# RF_433MHz.net
KiCad netlist of a schematic drawn in Altium Designer
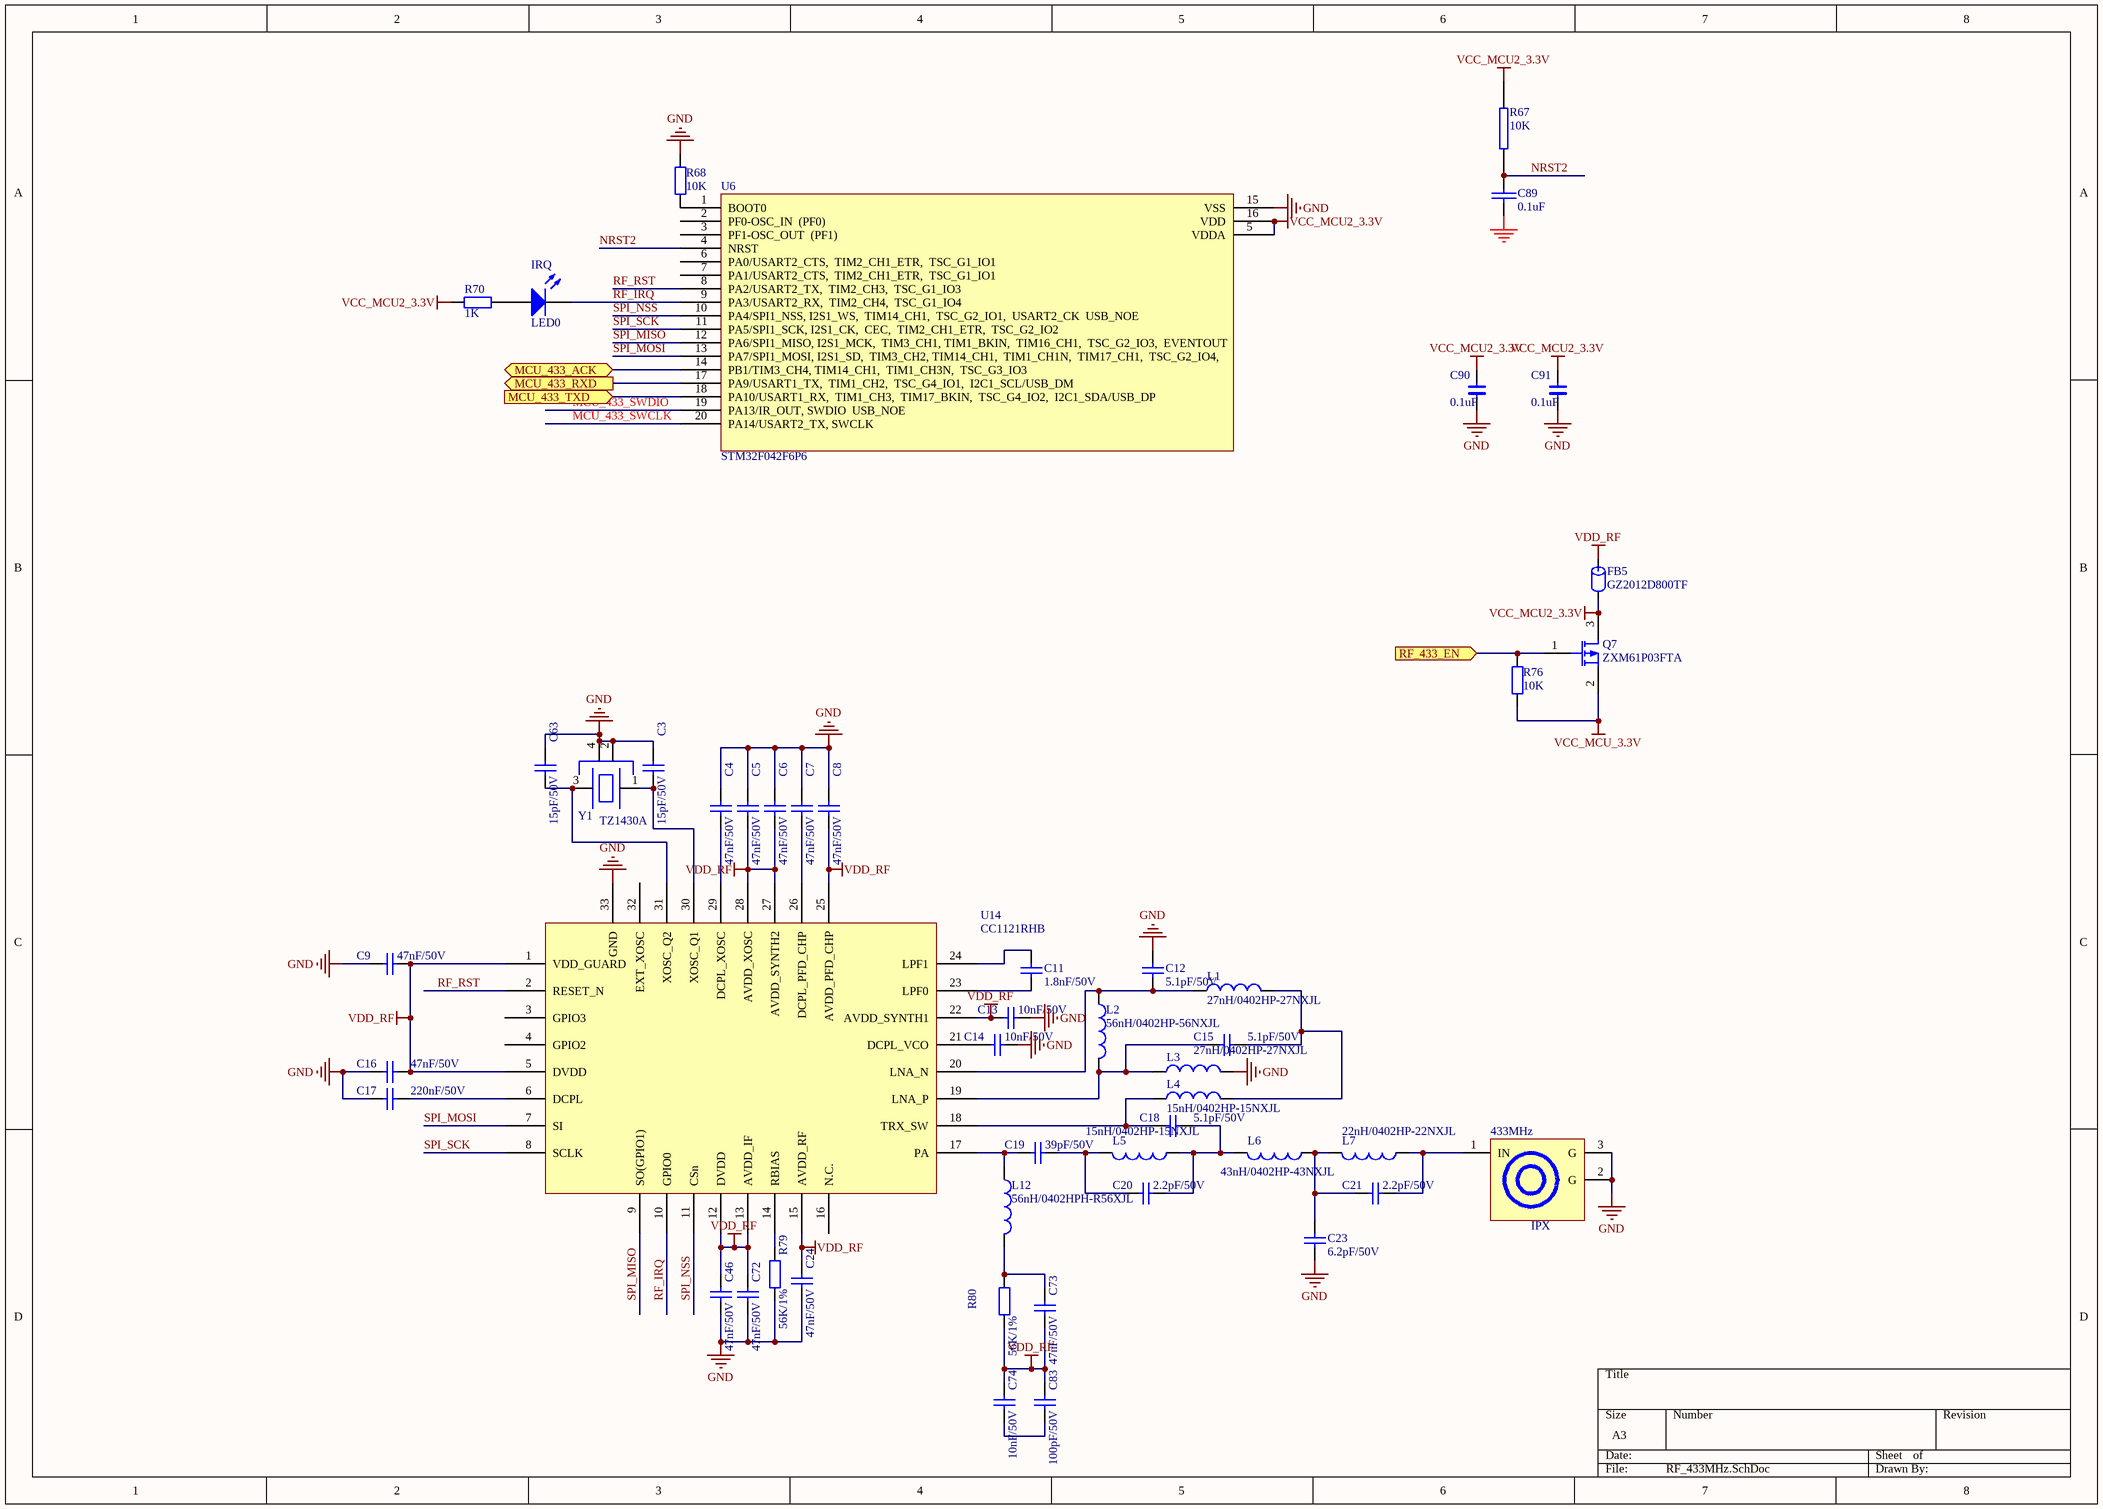
[diagram p0: RF_433MHz.SchDoc]

(export (version "E")
  (design (tool "Eeschema 10.0.6"))
  (components
    (comp (ref "433MHz")
      (value "IPX")
      (footprint "Pcblib_20110825:ECT8180001581")
      (description "MCU")
      (libsource (lib "MCU") (part "IPX"))
    )
    (comp (ref "C3")
      (value "15pF/50V")
      (footprint "0402C")
      (description "Capacitor SMD")
      (fields (field (name "PUBLISHER") "Altium Limited"))
      (libsource (lib "SX1276_e266v02a") (part "Cap"))
    )
    (comp (ref "C4")
      (value "47nF/50V")
      (footprint "0402C")
      (description "Capacitor SMD")
      (fields (field (name "PUBLISHER") "Altium Limited"))
      (libsource (lib "SX1276_e266v02a") (part "Cap"))
    )
    (comp (ref "C5")
      (value "47nF/50V")
      (footprint "0402C")
      (description "Capacitor SMD")
      (fields (field (name "PUBLISHER") "Altium Limited"))
      (libsource (lib "SX1276_e266v02a") (part "Cap"))
    )
    (comp (ref "C6")
      (value "47nF/50V")
      (footprint "0402C")
      (description "Capacitor SMD")
      (fields (field (name "PUBLISHER") "Altium Limited"))
      (libsource (lib "SX1276_e266v02a") (part "Cap"))
    )
    (comp (ref "C7")
      (value "47nF/50V")
      (footprint "0402C")
      (description "Capacitor SMD")
      (fields (field (name "PUBLISHER") "Altium Limited"))
      (libsource (lib "SX1276_e266v02a") (part "Cap"))
    )
    (comp (ref "C8")
      (value "47nF/50V")
      (footprint "0402C")
      (description "Capacitor SMD")
      (fields (field (name "PUBLISHER") "Altium Limited"))
      (libsource (lib "SX1276_e266v02a") (part "Cap"))
    )
    (comp (ref "C9")
      (value "47nF/50V")
      (footprint "0402C")
      (description "Capacitor SMD")
      (fields (field (name "PUBLISHER") "Altium Limited"))
      (libsource (lib "SX1276_e266v02a") (part "Cap"))
    )
    (comp (ref "C11")
      (value "1.8nF/50V")
      (footprint "0402C")
      (description "Capacitor SMD")
      (fields (field (name "PUBLISHER") "Altium Limited"))
      (libsource (lib "SX1276_e266v02a") (part "Cap"))
    )
    (comp (ref "C12")
      (value "5.1pF/50V")
      (footprint "0402C")
      (description "Capacitor SMD")
      (fields (field (name "PUBLISHER") "Altium Limited"))
      (libsource (lib "SX1276_e266v02a") (part "Cap"))
    )
    (comp (ref "C13")
      (value "10nF/50V")
      (footprint "0402C")
      (description "Capacitor SMD")
      (fields (field (name "PUBLISHER") "Altium Limited"))
      (libsource (lib "SX1276_e266v02a") (part "Cap"))
    )
    (comp (ref "C14")
      (value "10nF/50V")
      (footprint "0402C")
      (description "Capacitor SMD")
      (fields (field (name "PUBLISHER") "Altium Limited"))
      (libsource (lib "SX1276_e266v02a") (part "Cap"))
    )
    (comp (ref "C15")
      (value "5.1pF/50V")
      (footprint "0402C")
      (description "Capacitor SMD")
      (fields (field (name "PUBLISHER") "Altium Limited"))
      (libsource (lib "SX1276_e266v02a") (part "Cap"))
    )
    (comp (ref "C16")
      (value "47nF/50V")
      (footprint "0402C")
      (description "Capacitor SMD")
      (fields (field (name "PUBLISHER") "Altium Limited"))
      (libsource (lib "SX1276_e266v02a") (part "Cap"))
    )
    (comp (ref "C17")
      (value "220nF/50V")
      (footprint "0402C")
      (description "Capacitor SMD")
      (fields (field (name "PUBLISHER") "Altium Limited"))
      (libsource (lib "SX1276_e266v02a") (part "Cap"))
    )
    (comp (ref "C18")
      (value "5.1pF/50V")
      (footprint "0402C")
      (description "Capacitor SMD")
      (fields (field (name "PUBLISHER") "Altium Limited"))
      (libsource (lib "SX1276_e266v02a") (part "Cap"))
    )
    (comp (ref "C19")
      (value "39pF/50V")
      (footprint "0402C")
      (description "Capacitor SMD")
      (fields (field (name "PUBLISHER") "Altium Limited"))
      (libsource (lib "SX1276_e266v02a") (part "Cap"))
    )
    (comp (ref "C20")
      (value "2.2pF/50V")
      (footprint "0402C")
      (description "Capacitor SMD")
      (fields (field (name "PUBLISHER") "Altium Limited"))
      (libsource (lib "SX1276_e266v02a") (part "Cap"))
    )
    (comp (ref "C21")
      (value "2.2pF/50V")
      (footprint "0402C")
      (description "Capacitor SMD")
      (fields (field (name "PUBLISHER") "Altium Limited"))
      (libsource (lib "SX1276_e266v02a") (part "Cap"))
    )
    (comp (ref "C23")
      (value "6.2pF/50V")
      (footprint "0402C")
      (description "Capacitor SMD")
      (fields (field (name "PUBLISHER") "Altium Limited"))
      (libsource (lib "SX1276_e266v02a") (part "Cap"))
    )
    (comp (ref "C24")
      (value "47nF/50V")
      (footprint "0402C")
      (description "Capacitor SMD")
      (fields (field (name "PUBLISHER") "Altium Limited"))
      (libsource (lib "SX1276_e266v02a") (part "Cap"))
    )
    (comp (ref "C46")
      (value "47nF/50V")
      (footprint "0402C")
      (description "Capacitor SMD")
      (fields (field (name "PUBLISHER") "Altium Limited"))
      (libsource (lib "SX1276_e266v02a") (part "Cap"))
    )
    (comp (ref "C63")
      (value "15pF/50V")
      (footprint "0402C")
      (description "Capacitor SMD")
      (fields (field (name "PUBLISHER") "Altium Limited"))
      (libsource (lib "SX1276_e266v02a") (part "Cap"))
    )
    (comp (ref "C72")
      (value "47nF/50V")
      (footprint "0402C")
      (description "Capacitor SMD")
      (fields (field (name "PUBLISHER") "Altium Limited"))
      (libsource (lib "SX1276_e266v02a") (part "Cap"))
    )
    (comp (ref "C73")
      (value "47nF/50V")
      (footprint "0402C")
      (description "Capacitor SMD")
      (fields (field (name "PUBLISHER") "Altium Limited"))
      (libsource (lib "SX1276_e266v02a") (part "Cap"))
    )
    (comp (ref "C74")
      (value "10nF/50V")
      (footprint "0402C")
      (description "Capacitor SMD")
      (fields (field (name "PUBLISHER") "Altium Limited"))
      (libsource (lib "SX1276_e266v02a") (part "Cap"))
    )
    (comp (ref "C83")
      (value "100pF/50V")
      (footprint "0402C")
      (description "Capacitor SMD")
      (fields (field (name "PUBLISHER") "Altium Limited"))
      (libsource (lib "SX1276_e266v02a") (part "Cap"))
    )
    (comp (ref "C89")
      (value "0.1uF")
      (footprint "0603C")
      (description "Capacitor")
      (libsource (lib "*") (part "CAP"))
    )
    (comp (ref "C90")
      (value "0.1uF")
      (footprint "0603C")
      (description "C")
      (libsource (lib "Schlib_20110825") (part "C"))
    )
    (comp (ref "C91")
      (value "0.1uF")
      (footprint "0603C")
      (description "C")
      (libsource (lib "Schlib_20110825") (part "C"))
    )
    (comp (ref "FB5")
      (value "GZ2012D800TF")
      (footprint "0805CZ")
      (libsource (lib "Schlib_20110825") (part "FB"))
    )
    (comp (ref "IRQ")
      (value "LED0")
      (footprint "0603LED")
      (description "Typical INFRARED GaAs LED")
      (fields (field (name "PUBLISHER") "Altium Limited"))
      (libsource (lib "Miscellaneous Devices") (part "LED0"))
    )
    (comp (ref "L1")
      (value "27nH/0402HP-27NXJL")
      (footprint "0402R")
      (description "Inductor SMD")
      (fields (field (name "PUBLISHER") "Altium Limited"))
      (libsource (lib "SX1276_e266v02a") (part "Inductor"))
    )
    (comp (ref "L2")
      (value "56nH/0402HP-56NXJL")
      (footprint "0402R")
      (description "Inductor SMD")
      (fields (field (name "PUBLISHER") "Altium Limited"))
      (libsource (lib "SX1276_e266v02a") (part "Inductor"))
    )
    (comp (ref "L3")
      (value "27nH/0402HP-27NXJL")
      (footprint "0402R")
      (description "Inductor SMD")
      (fields (field (name "PUBLISHER") "Altium Limited"))
      (libsource (lib "SX1276_e266v02a") (part "Inductor"))
    )
    (comp (ref "L4")
      (value "15nH/0402HP-15NXJL")
      (footprint "0402R")
      (description "Inductor SMD")
      (fields (field (name "PUBLISHER") "Altium Limited"))
      (libsource (lib "SX1276_e266v02a") (part "Inductor"))
    )
    (comp (ref "L5")
      (value "15nH/0402HP-15NXJL")
      (footprint "0402R")
      (description "Inductor SMD")
      (fields (field (name "PUBLISHER") "Altium Limited"))
      (libsource (lib "SX1276_e266v02a") (part "Inductor"))
    )
    (comp (ref "L6")
      (value "43nH/0402HP-43NXJL")
      (footprint "0402R")
      (description "Inductor SMD")
      (fields (field (name "PUBLISHER") "Altium Limited"))
      (libsource (lib "SX1276_e266v02a") (part "Inductor"))
    )
    (comp (ref "L7")
      (value "22nH/0402HP-22NXJL")
      (footprint "0402R")
      (description "Inductor SMD")
      (fields (field (name "PUBLISHER") "Altium Limited"))
      (libsource (lib "SX1276_e266v02a") (part "Inductor"))
    )
    (comp (ref "L12")
      (value "56nH/0402HPH-R56XJL")
      (footprint "0402R")
      (description "Inductor SMD")
      (fields (field (name "PUBLISHER") "Altium Limited"))
      (libsource (lib "SX1276_e266v02a") (part "Inductor"))
    )
    (comp (ref "Q7")
      (value "ZXM61P03FTA")
      (footprint "SOT23-3")
      (description "ZXM61P03F")
      (fields (field (name "PUBLISHER") "Altium Limited"))
      (libsource (lib "Miscellaneous Devices") (part "MOSFET-P"))
    )
    (comp (ref "R67") (value "10K") (footprint "0603R") (libsource (lib "*") (part "RES2")))
    (comp (ref "R68")
      (value "10K")
      (footprint "0603R")
      (description "Resistor")
      (fields (field (name "PUBLISHER") "Altium Limited"))
      (libsource (lib "") (part "Res2_2"))
    )
    (comp (ref "R70")
      (value "1K")
      (footprint "0603R")
      (description "Resistor")
      (fields (field (name "PUBLISHER") "Altium Limited"))
      (libsource (lib "") (part "Res2_1"))
    )
    (comp (ref "R76")
      (value "10K")
      (footprint "0603R")
      (description "Resistor")
      (fields (field (name "PUBLISHER") "Altium Limited"))
      (libsource (lib "Miscellaneous Devices") (part "Res2"))
    )
    (comp (ref "R79")
      (value "56K/1%")
      (footprint "0603R")
      (description "Resistor")
      (fields (field (name "PUBLISHER") "Altium Limited"))
      (libsource (lib "Miscellaneous Devices") (part "Res2"))
    )
    (comp (ref "R80")
      (value "56K/1%")
      (footprint "0603R")
      (description "Resistor")
      (fields (field (name "PUBLISHER") "Altium Limited"))
      (libsource (lib "Miscellaneous Devices") (part "Res2"))
    )
    (comp (ref "U6")
      (value "STM32F042F6P6")
      (footprint "SOP65P640X265-20N")
      (libsource (lib "stm32") (part "STM32F042F6P6"))
    )
    (comp (ref "U14") (value "CC1121RHB") (libsource (lib "Schlib_20110825") (part "CC1121RHB")))
    (comp (ref "Y1")
      (value "TZ1430A")
      (footprint "OSCILLATOR-2.5X2.0")
      (libsource (lib "Myself_1") (part "XTAL3"))
    )
  )
  (nets
    (net (code "1") (name "/MCU_433_ACK") (class "Default")
      (node (ref "U6") (pin "14") (pinfunction "PB1/TIM3_CH4,_TIM14_CH1,__TIM1_CH3N,__TSC_G3_IO3_14") (pintype "passive"))
    )
    (net (code "2") (name "/MCU_433_RXD") (class "Default")
      (node (ref "U6") (pin "17") (pinfunction "PA9/USART1_TX,__TIM1_CH2,__TSC_G4_IO1,__I2C1_SCL/USB_DM_17") (pintype "passive"))
    )
    (net (code "3") (name "/MCU_433_SWCLK") (class "Default")
      (node (ref "U6") (pin "20") (pinfunction "PA14/USART2_TX,_SWCLK_20") (pintype "passive"))
    )
    (net (code "4") (name "/MCU_433_SWDIO") (class "Default")
      (node (ref "U6") (pin "19") (pinfunction "PA13/IR_OUT,_SWDIO__USB_NOE_19") (pintype "passive"))
    )
    (net (code "5") (name "/MCU_433_TXD") (class "Default")
      (node (ref "U6") (pin "18") (pinfunction "PA10/USART1_RX,__TIM1_CH3,__TIM17_BKIN,__TSC_G4_IO2,__I2C1_SDA/USB_DP_18") (pintype "passive"))
    )
    (net (code "6") (name "/NRST2") (class "Default")
      (node (ref "C89") (pin "1") (pinfunction "1_1") (pintype "passive"))
      (node (ref "R67") (pin "2") (pinfunction "2_2") (pintype "passive"))
      (node (ref "U6") (pin "4") (pinfunction "NRST_4") (pintype "passive"))
    )
    (net (code "7") (name "/RF_433_EN") (class "Default")
      (node (ref "Q7") (pin "1") (pinfunction "G_1") (pintype "passive"))
      (node (ref "R76") (pin "1") (pinfunction "1_1") (pintype "passive"))
    )
    (net (code "8") (name "/RF_IRQ") (class "Default")
      (node (ref "IRQ") (pin "2") (pinfunction "K_2") (pintype "passive"))
      (node (ref "U14") (pin "10") (pinfunction "GPIO0_10") (pintype "passive"))
      (node (ref "U6") (pin "9") (pinfunction "PA3/USART2_RX,__TIM2_CH4,__TSC_G1_IO4_9") (pintype "passive"))
    )
    (net (code "9") (name "/RF_RST") (class "Default")
      (node (ref "U14") (pin "2") (pinfunction "RESET_N_2") (pintype "passive"))
      (node (ref "U6") (pin "8") (pinfunction "PA2/USART2_TX,__TIM2_CH3,__TSC_G1_IO3_8") (pintype "passive"))
    )
    (net (code "10") (name "/SPI_MISO") (class "Default")
      (node (ref "U14") (pin "9") (pinfunction "SO(GPIO1)_9") (pintype "passive"))
      (node (ref "U6") (pin "12") (pinfunction "PA6/SPI1_MISO,_I2S1_MCK,__TIM3_CH1,_TIM1_BKIN,__TIM16_CH1,__TSC_G2_IO3,__EVENTOUT_12") (pintype "passive"))
    )
    (net (code "11") (name "/SPI_MOSI") (class "Default")
      (node (ref "U14") (pin "7") (pinfunction "SI_7") (pintype "passive"))
      (node (ref "U6") (pin "13") (pinfunction "PA7/SPI1_MOSI,_I2S1_SD,__TIM3_CH2,_TIM14_CH1,__TIM1_CH1N,__TIM17_CH1,__TSC_G2_IO4,_13") (pintype "passive"))
    )
    (net (code "12") (name "/SPI_NSS") (class "Default")
      (node (ref "U14") (pin "11") (pinfunction "CSn_11") (pintype "passive"))
      (node (ref "U6") (pin "10") (pinfunction "PA4/SPI1_NSS,_I2S1_WS,__TIM14_CH1,__TSC_G2_IO1,__USART2_CK__USB_NOE_10") (pintype "passive"))
    )
    (net (code "13") (name "/SPI_SCK") (class "Default")
      (node (ref "U14") (pin "8") (pinfunction "SCLK_8") (pintype "passive"))
      (node (ref "U6") (pin "11") (pinfunction "PA5/SPI1_SCK,_I2S1_CK,__CEC,__TIM2_CH1_ETR,__TSC_G2_IO2_11") (pintype "passive"))
    )
    (net (code "14") (name "GND") (class "Default")
      (node (ref "433MHz") (pin "2") (pinfunction "G_2") (pintype "passive"))
      (node (ref "433MHz") (pin "3") (pinfunction "G_3") (pintype "passive"))
      (node (ref "C12") (pin "1") (pinfunction "1_1") (pintype "passive"))
      (node (ref "C13") (pin "2") (pinfunction "2_2") (pintype "passive"))
      (node (ref "C14") (pin "2") (pinfunction "2_2") (pintype "passive"))
      (node (ref "C16") (pin "1") (pinfunction "1_1") (pintype "passive"))
      (node (ref "C17") (pin "1") (pinfunction "1_1") (pintype "passive"))
      (node (ref "C23") (pin "1") (pinfunction "1_1") (pintype "passive"))
      (node (ref "C24") (pin "1") (pinfunction "1_1") (pintype "passive"))
      (node (ref "C3") (pin "2") (pinfunction "2_2") (pintype "passive"))
      (node (ref "C4") (pin "2") (pinfunction "2_2") (pintype "passive"))
      (node (ref "C46") (pin "1") (pinfunction "1_1") (pintype "passive"))
      (node (ref "C5") (pin "2") (pinfunction "2_2") (pintype "passive"))
      (node (ref "C6") (pin "2") (pinfunction "2_2") (pintype "passive"))
      (node (ref "C63") (pin "2") (pinfunction "2_2") (pintype "passive"))
      (node (ref "C7") (pin "2") (pinfunction "2_2") (pintype "passive"))
      (node (ref "C72") (pin "1") (pinfunction "1_1") (pintype "passive"))
      (node (ref "C8") (pin "2") (pinfunction "2_2") (pintype "passive"))
      (node (ref "C89") (pin "2") (pinfunction "2_2") (pintype "passive"))
      (node (ref "C9") (pin "1") (pinfunction "1_1") (pintype "passive"))
      (node (ref "C90") (pin "1") (pintype "passive"))
      (node (ref "C91") (pin "1") (pintype "passive"))
      (node (ref "L3") (pin "2") (pinfunction "2_2") (pintype "passive"))
      (node (ref "R68") (pin "2") (pinfunction "2_2") (pintype "passive"))
      (node (ref "R79") (pin "2") (pinfunction "2_2") (pintype "passive"))
      (node (ref "U14") (pin "33") (pinfunction "GND_33") (pintype "passive"))
      (node (ref "U6") (pin "15") (pinfunction "VSS_15") (pintype "passive"))
      (node (ref "Y1") (pin "2") (pinfunction "GND_2") (pintype "passive"))
      (node (ref "Y1") (pin "4") (pinfunction "GND_4") (pintype "passive"))
    )
    (net (code "15") (name "Net-(433MHz-IN)") (class "Default")
      (node (ref "433MHz") (pin "1") (pinfunction "IN_1") (pintype "passive"))
      (node (ref "C21") (pin "2") (pinfunction "2_2") (pintype "passive"))
      (node (ref "L7") (pin "1") (pinfunction "1_1") (pintype "passive"))
    )
    (net (code "16") (name "Net-(C15-Pad1)") (class "Default")
      (node (ref "C15") (pin "1") (pinfunction "1_1") (pintype "passive"))
      (node (ref "L1") (pin "2") (pinfunction "2_2") (pintype "passive"))
      (node (ref "L4") (pin "2") (pinfunction "2_2") (pintype "passive"))
    )
    (net (code "17") (name "Net-(C18-Pad1)") (class "Default")
      (node (ref "C18") (pin "1") (pinfunction "1_1") (pintype "passive"))
      (node (ref "C20") (pin "2") (pinfunction "2_2") (pintype "passive"))
      (node (ref "L5") (pin "1") (pinfunction "1_1") (pintype "passive"))
      (node (ref "L6") (pin "2") (pinfunction "2_2") (pintype "passive"))
    )
    (net (code "18") (name "Net-(C19-Pad2)") (class "Default")
      (node (ref "C19") (pin "2") (pinfunction "2_2") (pintype "passive"))
      (node (ref "C20") (pin "1") (pinfunction "1_1") (pintype "passive"))
      (node (ref "L5") (pin "2") (pinfunction "2_2") (pintype "passive"))
    )
    (net (code "19") (name "Net-(C21-Pad1)") (class "Default")
      (node (ref "C21") (pin "1") (pinfunction "1_1") (pintype "passive"))
      (node (ref "C23") (pin "2") (pinfunction "2_2") (pintype "passive"))
      (node (ref "L6") (pin "1") (pinfunction "1_1") (pintype "passive"))
      (node (ref "L7") (pin "2") (pinfunction "2_2") (pintype "passive"))
    )
    (net (code "20") (name "Net-(C73-Pad2)") (class "Default")
      (node (ref "C73") (pin "2") (pinfunction "2_2") (pintype "passive"))
      (node (ref "L12") (pin "2") (pinfunction "2_2") (pintype "passive"))
      (node (ref "R80") (pin "1") (pinfunction "1_1") (pintype "passive"))
    )
    (net (code "21") (name "Net-(C74-Pad1)") (class "Default")
      (node (ref "C74") (pin "1") (pinfunction "1_1") (pintype "passive"))
      (node (ref "C83") (pin "1") (pinfunction "1_1") (pintype "passive"))
    )
    (net (code "22") (name "Net-(IRQ-A)") (class "Default")
      (node (ref "IRQ") (pin "1") (pinfunction "A_1") (pintype "passive"))
      (node (ref "R70") (pin "2") (pinfunction "2_2") (pintype "passive"))
    )
    (net (code "23") (name "Net-(U6-BOOT0)") (class "Default")
      (node (ref "R68") (pin "1") (pinfunction "1_1") (pintype "passive"))
      (node (ref "U6") (pin "1") (pinfunction "BOOT0_1") (pintype "passive"))
    )
    (net (code "24") (name "Net-(U14-DCPL)") (class "Default")
      (node (ref "C17") (pin "2") (pinfunction "2_2") (pintype "passive"))
      (node (ref "U14") (pin "6") (pinfunction "DCPL_6") (pintype "passive"))
    )
    (net (code "25") (name "Net-(U14-DCPL_PFD_CHP)") (class "Default")
      (node (ref "C7") (pin "1") (pinfunction "1_1") (pintype "passive"))
      (node (ref "U14") (pin "26") (pinfunction "DCPL_PFD_CHP_26") (pintype "passive"))
    )
    (net (code "26") (name "Net-(U14-DCPL_VCO)") (class "Default")
      (node (ref "C14") (pin "1") (pinfunction "1_1") (pintype "passive"))
      (node (ref "U14") (pin "21") (pinfunction "DCPL_VCO_21") (pintype "passive"))
    )
    (net (code "27") (name "Net-(U14-DCPL_XOSC)") (class "Default")
      (node (ref "C4") (pin "1") (pinfunction "1_1") (pintype "passive"))
      (node (ref "U14") (pin "29") (pinfunction "DCPL_XOSC_29") (pintype "passive"))
    )
    (net (code "28") (name "Net-(U14-LNA_N)") (class "Default")
      (node (ref "C12") (pin "2") (pinfunction "2_2") (pintype "passive"))
      (node (ref "L1") (pin "1") (pinfunction "1_1") (pintype "passive"))
      (node (ref "L2") (pin "1") (pinfunction "1_1") (pintype "passive"))
      (node (ref "U14") (pin "20") (pinfunction "LNA_N_20") (pintype "passive"))
    )
    (net (code "29") (name "Net-(U14-LNA_P)") (class "Default")
      (node (ref "C15") (pin "2") (pinfunction "2_2") (pintype "passive"))
      (node (ref "L2") (pin "2") (pinfunction "2_2") (pintype "passive"))
      (node (ref "L3") (pin "1") (pinfunction "1_1") (pintype "passive"))
      (node (ref "U14") (pin "19") (pinfunction "LNA_P_19") (pintype "passive"))
    )
    (net (code "30") (name "Net-(U14-LPF0)") (class "Default")
      (node (ref "C11") (pin "1") (pinfunction "1_1") (pintype "passive"))
      (node (ref "U14") (pin "23") (pinfunction "LPF0_23") (pintype "passive"))
    )
    (net (code "31") (name "Net-(U14-LPF1)") (class "Default")
      (node (ref "C11") (pin "2") (pinfunction "2_2") (pintype "passive"))
      (node (ref "U14") (pin "24") (pinfunction "LPF1_24") (pintype "passive"))
    )
    (net (code "32") (name "Net-(U14-PA)") (class "Default")
      (node (ref "C19") (pin "1") (pinfunction "1_1") (pintype "passive"))
      (node (ref "L12") (pin "1") (pinfunction "1_1") (pintype "passive"))
      (node (ref "U14") (pin "17") (pinfunction "PA_17") (pintype "passive"))
    )
    (net (code "33") (name "Net-(U14-RBIAS)") (class "Default")
      (node (ref "R79") (pin "1") (pinfunction "1_1") (pintype "passive"))
      (node (ref "U14") (pin "14") (pinfunction "RBIAS_14") (pintype "passive"))
    )
    (net (code "34") (name "Net-(U14-TRX_SW)") (class "Default")
      (node (ref "C18") (pin "2") (pinfunction "2_2") (pintype "passive"))
      (node (ref "L4") (pin "1") (pinfunction "1_1") (pintype "passive"))
      (node (ref "U14") (pin "18") (pinfunction "TRX_SW_18") (pintype "passive"))
    )
    (net (code "35") (name "Net-(U14-XOSC_Q1)") (class "Default")
      (node (ref "C3") (pin "1") (pinfunction "1_1") (pintype "passive"))
      (node (ref "U14") (pin "30") (pinfunction "XOSC_Q1_30") (pintype "passive"))
      (node (ref "Y1") (pin "1") (pinfunction "1_1") (pintype "passive"))
    )
    (net (code "36") (name "Net-(U14-XOSC_Q2)") (class "Default")
      (node (ref "C63") (pin "1") (pinfunction "1_1") (pintype "passive"))
      (node (ref "U14") (pin "31") (pinfunction "XOSC_Q2_31") (pintype "passive"))
      (node (ref "Y1") (pin "3") (pinfunction "3_3") (pintype "passive"))
    )
    (net (code "37") (name "VCC_MCU2_3.3V") (class "Default")
      (node (ref "C90") (pin "2") (pintype "passive"))
      (node (ref "C91") (pin "2") (pintype "passive"))
      (node (ref "FB5") (pin "2") (pintype "passive"))
      (node (ref "Q7") (pin "3") (pinfunction "S_3") (pintype "passive"))
      (node (ref "R67") (pin "1") (pinfunction "1_1") (pintype "passive"))
      (node (ref "R70") (pin "1") (pinfunction "1_1") (pintype "passive"))
      (node (ref "U6") (pin "16") (pinfunction "VDD_16") (pintype "passive"))
      (node (ref "U6") (pin "5") (pinfunction "VDDA_5") (pintype "passive"))
    )
    (net (code "38") (name "VCC_MCU_3.3V") (class "Default")
      (node (ref "Q7") (pin "2") (pinfunction "D_2") (pintype "passive"))
      (node (ref "R76") (pin "2") (pinfunction "2_2") (pintype "passive"))
    )
    (net (code "39") (name "VDD_RF") (class "Default")
      (node (ref "C13") (pin "1") (pinfunction "1_1") (pintype "passive"))
      (node (ref "C16") (pin "2") (pinfunction "2_2") (pintype "passive"))
      (node (ref "C24") (pin "2") (pinfunction "2_2") (pintype "passive"))
      (node (ref "C46") (pin "2") (pinfunction "2_2") (pintype "passive"))
      (node (ref "C5") (pin "1") (pinfunction "1_1") (pintype "passive"))
      (node (ref "C6") (pin "1") (pinfunction "1_1") (pintype "passive"))
      (node (ref "C72") (pin "2") (pinfunction "2_2") (pintype "passive"))
      (node (ref "C73") (pin "1") (pinfunction "1_1") (pintype "passive"))
      (node (ref "C74") (pin "2") (pinfunction "2_2") (pintype "passive"))
      (node (ref "C8") (pin "1") (pinfunction "1_1") (pintype "passive"))
      (node (ref "C83") (pin "2") (pinfunction "2_2") (pintype "passive"))
      (node (ref "C9") (pin "2") (pinfunction "2_2") (pintype "passive"))
      (node (ref "FB5") (pin "1") (pintype "passive"))
      (node (ref "R80") (pin "2") (pinfunction "2_2") (pintype "passive"))
      (node (ref "U14") (pin "1") (pinfunction "VDD_GUARD_1") (pintype "passive"))
      (node (ref "U14") (pin "12") (pinfunction "DVDD_12") (pintype "passive"))
      (node (ref "U14") (pin "13") (pinfunction "AVDD_IF_13") (pintype "passive"))
      (node (ref "U14") (pin "15") (pinfunction "AVDD_RF_15") (pintype "passive"))
      (node (ref "U14") (pin "22") (pinfunction "AVDD_SYNTH1_22") (pintype "passive"))
      (node (ref "U14") (pin "25") (pinfunction "AVDD_PFD_CHP_25") (pintype "passive"))
      (node (ref "U14") (pin "27") (pinfunction "AVDD_SYNTH2_27") (pintype "passive"))
      (node (ref "U14") (pin "28") (pinfunction "AVDD_XOSC_28") (pintype "passive"))
      (node (ref "U14") (pin "5") (pinfunction "DVDD_5") (pintype "passive"))
    )
    (net (code "40") (name "unconnected-(U6-PA0{slash}USART2_CTS,__TIM2_CH1_ETR,__TSC_G1_IO1-Pad6)") (class "Default")
      (node (ref "U6") (pin "6") (pinfunction "PA0/USART2_CTS,__TIM2_CH1_ETR,__TSC_G1_IO1_6") (pintype "passive"))
    )
    (net (code "41") (name "unconnected-(U6-PA1{slash}USART2_CTS,__TIM2_CH1_ETR,__TSC_G1_IO1-Pad7)") (class "Default")
      (node (ref "U6") (pin "7") (pinfunction "PA1/USART2_CTS,__TIM2_CH1_ETR,__TSC_G1_IO1_7") (pintype "passive"))
    )
    (net (code "42") (name "unconnected-(U6-PF0-OSC_IN__(PF0)-Pad2)") (class "Default")
      (node (ref "U6") (pin "2") (pinfunction "PF0-OSC_IN__(PF0)_2") (pintype "passive"))
    )
    (net (code "43") (name "unconnected-(U6-PF1-OSC_OUT__(PF1)-Pad3)") (class "Default")
      (node (ref "U6") (pin "3") (pinfunction "PF1-OSC_OUT__(PF1)_3") (pintype "passive"))
    )
    (net (code "44") (name "unconnected-(U14-EXT_XOSC-Pad32)") (class "Default")
      (node (ref "U14") (pin "32") (pinfunction "EXT_XOSC_32") (pintype "passive"))
    )
    (net (code "45") (name "unconnected-(U14-GPIO2-Pad4)") (class "Default")
      (node (ref "U14") (pin "4") (pinfunction "GPIO2_4") (pintype "passive"))
    )
    (net (code "46") (name "unconnected-(U14-GPIO3-Pad3)") (class "Default")
      (node (ref "U14") (pin "3") (pinfunction "GPIO3_3") (pintype "passive"))
    )
    (net (code "47") (name "unconnected-(U14-N.C.-Pad16)") (class "Default")
      (node (ref "U14") (pin "16") (pinfunction "N.C._16") (pintype "passive"))
    )
  )
)
